# Sheet1.net
KiCad netlist of a schematic drawn in Altium Designer
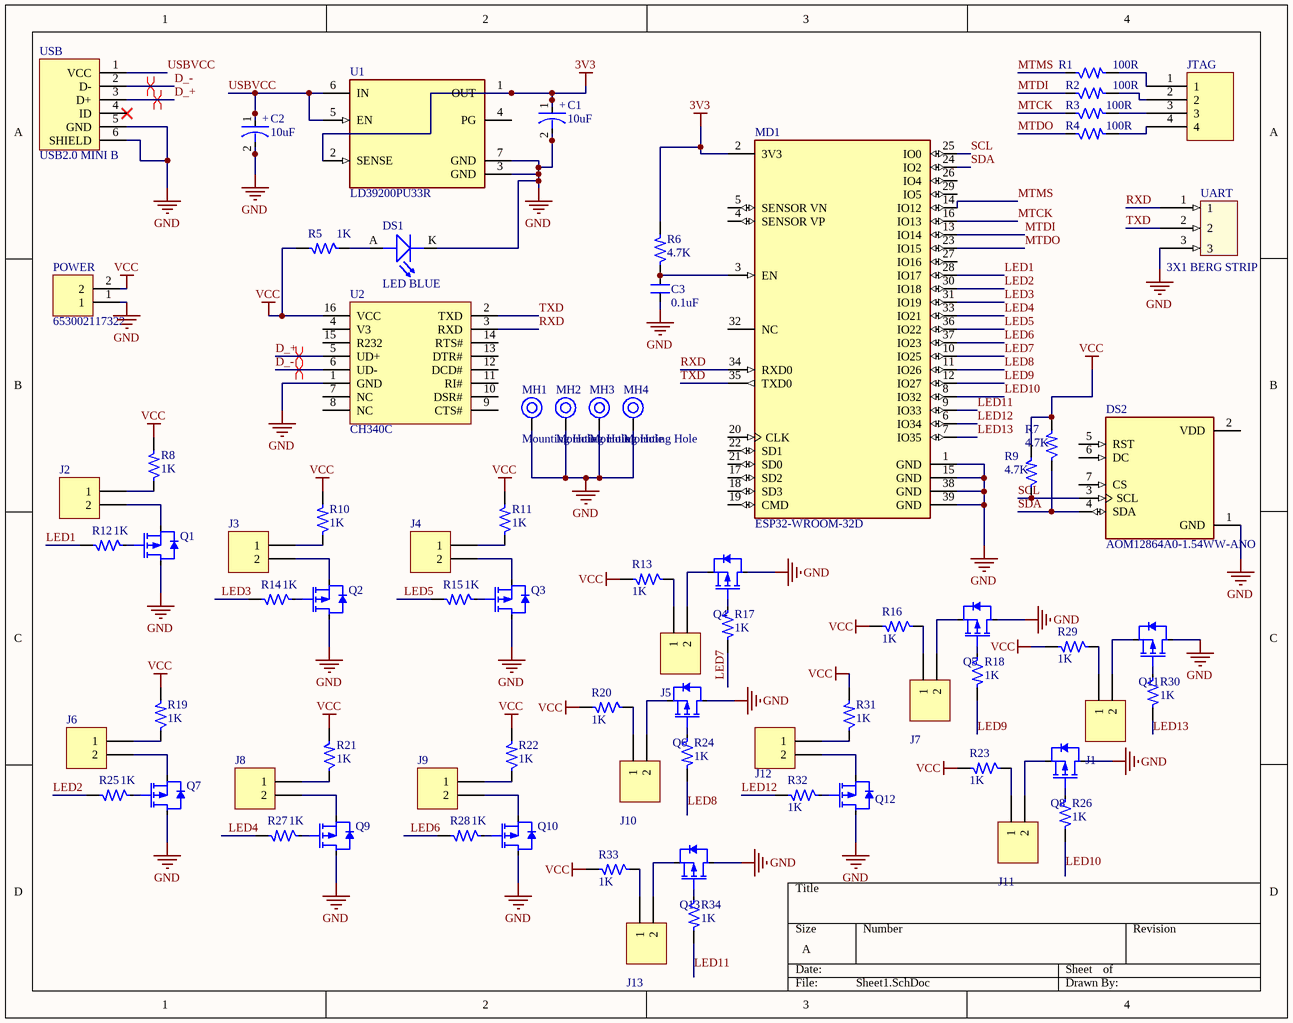
[diagram p0: Sheet1.SchDoc]

(export (version "E")
  (design (tool "Eeschema 10.0.6"))
  (components
    (comp (ref "C1")
      (value "10uF")
      (footprint "ACAP_P339_D393_H531_RAD")
      (description "10µF 400V Aluminum Electrolytic Capacitors Radial, Can - SMD 10000 Hrs @ 105°C")
      (fields
        (field (name "MANUFACTURER") "Nichicon")
        (field (name "MANUFACTURER PART NUMBER") "ULV2G100MNL1GS")
      )
      (libsource (lib "ESTEEMPCBLIB") (part "CAP-P_10uF-400V-20%-RAD"))
    )
    (comp (ref "C2")
      (value "10uF")
      (footprint "ACAP_P339_D393_H531_RAD")
      (description "10µF 400V Aluminum Electrolytic Capacitors Radial, Can - SMD 10000 Hrs @ 105°C")
      (fields
        (field (name "MANUFACTURER") "Nichicon")
        (field (name "MANUFACTURER PART NUMBER") "ULV2G100MNL1GS")
      )
      (libsource (lib "ESTEEMPCBLIB") (part "CAP-P_10uF-400V-20%-RAD"))
    )
    (comp (ref "C3")
      (value "0.1uF")
      (footprint "CAP_0805")
      (description "0.1µF ±5% 50V Ceramic Capacitor X7R 0805 (2012 Metric)")
      (fields
        (field (name "MANUFACTURER") "AVX Corporation")
        (field (name "MANUFACTURER PART NUMBER") "08055C104JAT4A")
      )
      (libsource (lib "ESTEEMPCBLIB") (part "CAP_0.1uF-50V-5%-0805"))
    )
    (comp (ref "DS1")
      (value "LED BLUE")
      (footprint "LED_0805")
      (description "Blue 470nm LED Indication - Discrete 3.3V 0805 (2012 Metric)")
      (fields
        (field (name "MANUFACTURER") "Vishay Lite-On")
        (field (name "MANUFACTURER PART NUMBER") "LTST-C171TBKT")
      )
      (libsource (lib "ESTEEMPCBLIB") (part "LED_BLUE-3V3-20mA-0805"))
    )
    (comp (ref "DS2")
      (value "AOM12864A0-1.54WW-ANO")
      (footprint "LCD_AOM12864A0-1.54WW-ANO")
      (description "Non-Touch Graphic LCD Display Module - White OLED SPI 1.54 (39.12mm) 128 x 64")
      (fields (field (name "MF") "Orient Display"))
      (libsource (lib "AOM12864A0-1.54WW-ANO") (part "AOM12864A0-1.54WW-ANO"))
    )
    (comp (ref "J1")
      (value "2X1 TERMINAL BLOCK")
      (footprint "CON2_P137_691103110002_TH_ST")
      (description "2 Pins, 1 Row 137mil Pitch, straight Connector, male")
      (fields
        (field (name "MANUFACTURER") "Wurth Electronics")
        (field (name "MANUFACTURER PART NUMBER") "691103110002")
      )
      (libsource (lib "") (part "CON-TB_2X1-137-ST-TH_1"))
    )
    (comp (ref "J2")
      (value "2X1 TERMINAL BLOCK")
      (footprint "CON2_P137_691103110002_TH_ST")
      (description "2 Pins, 1 Row 137mil Pitch, straight Connector, male")
      (fields
        (field (name "MANUFACTURER") "Wurth Electronics")
        (field (name "MANUFACTURER PART NUMBER") "691103110002")
      )
      (libsource (lib "ESTEEMPCBLIB") (part "CON-TB_2X1-137-ST-TH"))
    )
    (comp (ref "J3")
      (value "2X1 TERMINAL BLOCK")
      (footprint "CON2_P137_691103110002_TH_ST")
      (description "2 Pins, 1 Row 137mil Pitch, straight Connector, male")
      (fields
        (field (name "MANUFACTURER") "Wurth Electronics")
        (field (name "MANUFACTURER PART NUMBER") "691103110002")
      )
      (libsource (lib "ESTEEMPCBLIB") (part "CON-TB_2X1-137-ST-TH"))
    )
    (comp (ref "J4")
      (value "2X1 TERMINAL BLOCK")
      (footprint "CON2_P137_691103110002_TH_ST")
      (description "2 Pins, 1 Row 137mil Pitch, straight Connector, male")
      (fields
        (field (name "MANUFACTURER") "Wurth Electronics")
        (field (name "MANUFACTURER PART NUMBER") "691103110002")
      )
      (libsource (lib "ESTEEMPCBLIB") (part "CON-TB_2X1-137-ST-TH"))
    )
    (comp (ref "J5")
      (value "2X1 TERMINAL BLOCK")
      (footprint "CON2_P137_691103110002_TH_ST")
      (description "2 Pins, 1 Row 137mil Pitch, straight Connector, male")
      (fields
        (field (name "MANUFACTURER") "Wurth Electronics")
        (field (name "MANUFACTURER PART NUMBER") "691103110002")
      )
      (libsource (lib "") (part "CON-TB_2X1-137-ST-TH_1"))
    )
    (comp (ref "J6")
      (value "2X1 TERMINAL BLOCK")
      (footprint "CON2_P137_691103110002_TH_ST")
      (description "2 Pins, 1 Row 137mil Pitch, straight Connector, male")
      (fields
        (field (name "MANUFACTURER") "Wurth Electronics")
        (field (name "MANUFACTURER PART NUMBER") "691103110002")
      )
      (libsource (lib "ESTEEMPCBLIB") (part "CON-TB_2X1-137-ST-TH"))
    )
    (comp (ref "J7")
      (value "2X1 TERMINAL BLOCK")
      (footprint "CON2_P137_691103110002_TH_ST")
      (description "2 Pins, 1 Row 137mil Pitch, straight Connector, male")
      (fields
        (field (name "MANUFACTURER") "Wurth Electronics")
        (field (name "MANUFACTURER PART NUMBER") "691103110002")
      )
      (libsource (lib "") (part "CON-TB_2X1-137-ST-TH_1"))
    )
    (comp (ref "J8")
      (value "2X1 TERMINAL BLOCK")
      (footprint "CON2_P137_691103110002_TH_ST")
      (description "2 Pins, 1 Row 137mil Pitch, straight Connector, male")
      (fields
        (field (name "MANUFACTURER") "Wurth Electronics")
        (field (name "MANUFACTURER PART NUMBER") "691103110002")
      )
      (libsource (lib "ESTEEMPCBLIB") (part "CON-TB_2X1-137-ST-TH"))
    )
    (comp (ref "J9")
      (value "2X1 TERMINAL BLOCK")
      (footprint "CON2_P137_691103110002_TH_ST")
      (description "2 Pins, 1 Row 137mil Pitch, straight Connector, male")
      (fields
        (field (name "MANUFACTURER") "Wurth Electronics")
        (field (name "MANUFACTURER PART NUMBER") "691103110002")
      )
      (libsource (lib "ESTEEMPCBLIB") (part "CON-TB_2X1-137-ST-TH"))
    )
    (comp (ref "J10")
      (value "2X1 TERMINAL BLOCK")
      (footprint "CON2_P137_691103110002_TH_ST")
      (description "2 Pins, 1 Row 137mil Pitch, straight Connector, male")
      (fields
        (field (name "MANUFACTURER") "Wurth Electronics")
        (field (name "MANUFACTURER PART NUMBER") "691103110002")
      )
      (libsource (lib "") (part "CON-TB_2X1-137-ST-TH_1"))
    )
    (comp (ref "J11")
      (value "2X1 TERMINAL BLOCK")
      (footprint "CON2_P137_691103110002_TH_ST")
      (description "2 Pins, 1 Row 137mil Pitch, straight Connector, male")
      (fields
        (field (name "MANUFACTURER") "Wurth Electronics")
        (field (name "MANUFACTURER PART NUMBER") "691103110002")
      )
      (libsource (lib "") (part "CON-TB_2X1-137-ST-TH_1"))
    )
    (comp (ref "J12")
      (value "2X1 TERMINAL BLOCK")
      (footprint "CON2_P137_691103110002_TH_ST")
      (description "2 Pins, 1 Row 137mil Pitch, straight Connector, male")
      (fields
        (field (name "MANUFACTURER") "Wurth Electronics")
        (field (name "MANUFACTURER PART NUMBER") "691103110002")
      )
      (libsource (lib "ESTEEMPCBLIB") (part "CON-TB_2X1-137-ST-TH"))
    )
    (comp (ref "J13")
      (value "2X1 TERMINAL BLOCK")
      (footprint "CON2_P137_691103110002_TH_ST")
      (description "2 Pins, 1 Row 137mil Pitch, straight Connector, male")
      (fields
        (field (name "MANUFACTURER") "Wurth Electronics")
        (field (name "MANUFACTURER PART NUMBER") "691103110002")
      )
      (libsource (lib "") (part "CON-TB_2X1-137-ST-TH_1"))
    )
    (comp (ref "JTAG")
      (value "4X1 BERG STRIP")
      (footprint "CON4_100_40D72_TH_ST_MALE")
      (description "4 Pins, 1 Row 2.54mm Pitch, Straight bergstrip, Male")
      (fields (field (name "MANUFACTURER") "NA"))
      (libsource (lib "ESTEEMPCBLIB") (part "CON-BS-PLG_4X1-100-ST-TH"))
    )
    (comp (ref "MD1")
      (value "ESP32-WROOM-32D")
      (footprint "FP-ESP32-WROOM-32D-MFG")
      (description "WIFI MODULE 32MBITS SPI FLASH")
      (fields
        (field (name "OCTOPART") "https://octopart.com/esp32-wroom-32d-espressif+systems-91040050")
        (field (name "MANUFACTURER") "Espressif Systems")
      )
      (libsource (lib "Altium Content Vault") (part "a031a76f8c27026a7a7f4657ff233a3"))
    )
    (comp (ref "MH1")
      (value "Mounting Hole")
      (footprint "MOUNTING")
      (fields (field (name "MANUFACTURER PART NUMBER") "NA"))
      (libsource (lib "ESTEEMPCBLIB") (part "MH_3.5H_6D"))
    )
    (comp (ref "MH2")
      (value "Mounting Hole")
      (footprint "MOUNTING")
      (fields (field (name "MANUFACTURER PART NUMBER") "NA"))
      (libsource (lib "ESTEEMPCBLIB") (part "MH_3.5H_6D"))
    )
    (comp (ref "MH3")
      (value "Mounting Hole")
      (footprint "MOUNTING")
      (fields (field (name "MANUFACTURER PART NUMBER") "NA"))
      (libsource (lib "ESTEEMPCBLIB") (part "MH_3.5H_6D"))
    )
    (comp (ref "MH4")
      (value "Mounting Hole")
      (footprint "MOUNTING")
      (fields (field (name "MANUFACTURER PART NUMBER") "NA"))
      (libsource (lib "ESTEEMPCBLIB") (part "MH_3.5H_6D"))
    )
    (comp (ref "POWER")
      (value "653002117322")
      (footprint "CON2_50_653002117322_TH_RA")
      (description "1 Pins, 1 Row 256mil Pitch, Straight, Male")
      (fields (field (name "MANUFACTURER") "JST") (field (name "MATING PART NUMBER") "653002113322"))
      (libsource (lib "ESTEEMPCBLIB") (part "CON-PLG_2X1-50-RA-TH"))
    )
    (comp (ref "Q1")
      (value "SUD19P06-60-GE3")
      (footprint "TO-252_181_255_118X62_SMD")
      (description "P-Channel 60V 18.3A (Tc) 2.3W (Ta), 38.5W (Tc) Surface Mount TO-252, (D-Pak)")
      (fields (field (name "MANUFACTURER") "Vishay Siliconix"))
      (libsource (lib "ESTEEMPCBLIB") (part "MOSFET-P_60V-18A-TO252"))
    )
    (comp (ref "Q2")
      (value "SUD19P06-60-GE3")
      (footprint "TO-252_181_255_118X62_SMD")
      (description "P-Channel 60V 18.3A (Tc) 2.3W (Ta), 38.5W (Tc) Surface Mount TO-252, (D-Pak)")
      (fields (field (name "MANUFACTURER") "Vishay Siliconix"))
      (libsource (lib "ESTEEMPCBLIB") (part "MOSFET-P_60V-18A-TO252"))
    )
    (comp (ref "Q3")
      (value "SUD19P06-60-GE3")
      (footprint "TO-252_181_255_118X62_SMD")
      (description "P-Channel 60V 18.3A (Tc) 2.3W (Ta), 38.5W (Tc) Surface Mount TO-252, (D-Pak)")
      (fields (field (name "MANUFACTURER") "Vishay Siliconix"))
      (libsource (lib "ESTEEMPCBLIB") (part "MOSFET-P_60V-18A-TO252"))
    )
    (comp (ref "Q4")
      (value "SUD19P06-60-GE3")
      (footprint "TO-252_181_255_118X62_SMD")
      (description "P-Channel 60V 18.3A (Tc) 2.3W (Ta), 38.5W (Tc) Surface Mount TO-252, (D-Pak)")
      (fields (field (name "MANUFACTURER") "Vishay Siliconix"))
      (libsource (lib "ESTEEMPCBLIB") (part "MOSFET-P_60V-18A-TO252"))
    )
    (comp (ref "Q5")
      (value "SUD19P06-60-GE3")
      (footprint "TO-252_181_255_118X62_SMD")
      (description "P-Channel 60V 18.3A (Tc) 2.3W (Ta), 38.5W (Tc) Surface Mount TO-252, (D-Pak)")
      (fields (field (name "MANUFACTURER") "Vishay Siliconix"))
      (libsource (lib "ESTEEMPCBLIB") (part "MOSFET-P_60V-18A-TO252"))
    )
    (comp (ref "Q6")
      (value "SUD19P06-60-GE3")
      (footprint "TO-252_181_255_118X62_SMD")
      (description "P-Channel 60V 18.3A (Tc) 2.3W (Ta), 38.5W (Tc) Surface Mount TO-252, (D-Pak)")
      (fields (field (name "MANUFACTURER") "Vishay Siliconix"))
      (libsource (lib "ESTEEMPCBLIB") (part "MOSFET-P_60V-18A-TO252"))
    )
    (comp (ref "Q7")
      (value "SUD19P06-60-GE3")
      (footprint "TO-252_181_255_118X62_SMD")
      (description "P-Channel 60V 18.3A (Tc) 2.3W (Ta), 38.5W (Tc) Surface Mount TO-252, (D-Pak)")
      (fields (field (name "MANUFACTURER") "Vishay Siliconix"))
      (libsource (lib "ESTEEMPCBLIB") (part "MOSFET-P_60V-18A-TO252"))
    )
    (comp (ref "Q8")
      (value "SUD19P06-60-GE3")
      (footprint "TO-252_181_255_118X62_SMD")
      (description "P-Channel 60V 18.3A (Tc) 2.3W (Ta), 38.5W (Tc) Surface Mount TO-252, (D-Pak)")
      (fields (field (name "MANUFACTURER") "Vishay Siliconix"))
      (libsource (lib "ESTEEMPCBLIB") (part "MOSFET-P_60V-18A-TO252"))
    )
    (comp (ref "Q9")
      (value "SUD19P06-60-GE3")
      (footprint "TO-252_181_255_118X62_SMD")
      (description "P-Channel 60V 18.3A (Tc) 2.3W (Ta), 38.5W (Tc) Surface Mount TO-252, (D-Pak)")
      (fields (field (name "MANUFACTURER") "Vishay Siliconix"))
      (libsource (lib "ESTEEMPCBLIB") (part "MOSFET-P_60V-18A-TO252"))
    )
    (comp (ref "Q10")
      (value "SUD19P06-60-GE3")
      (footprint "TO-252_181_255_118X62_SMD")
      (description "P-Channel 60V 18.3A (Tc) 2.3W (Ta), 38.5W (Tc) Surface Mount TO-252, (D-Pak)")
      (fields (field (name "MANUFACTURER") "Vishay Siliconix"))
      (libsource (lib "ESTEEMPCBLIB") (part "MOSFET-P_60V-18A-TO252"))
    )
    (comp (ref "Q11")
      (value "SUD19P06-60-GE3")
      (footprint "TO-252_181_255_118X62_SMD")
      (description "P-Channel 60V 18.3A (Tc) 2.3W (Ta), 38.5W (Tc) Surface Mount TO-252, (D-Pak)")
      (fields (field (name "MANUFACTURER") "Vishay Siliconix"))
      (libsource (lib "ESTEEMPCBLIB") (part "MOSFET-P_60V-18A-TO252"))
    )
    (comp (ref "Q12")
      (value "SUD19P06-60-GE3")
      (footprint "TO-252_181_255_118X62_SMD")
      (description "P-Channel 60V 18.3A (Tc) 2.3W (Ta), 38.5W (Tc) Surface Mount TO-252, (D-Pak)")
      (fields (field (name "MANUFACTURER") "Vishay Siliconix"))
      (libsource (lib "ESTEEMPCBLIB") (part "MOSFET-P_60V-18A-TO252"))
    )
    (comp (ref "Q13")
      (value "SUD19P06-60-GE3")
      (footprint "TO-252_181_255_118X62_SMD")
      (description "P-Channel 60V 18.3A (Tc) 2.3W (Ta), 38.5W (Tc) Surface Mount TO-252, (D-Pak)")
      (fields (field (name "MANUFACTURER") "Vishay Siliconix"))
      (libsource (lib "ESTEEMPCBLIB") (part "MOSFET-P_60V-18A-TO252"))
    )
    (comp (ref "R1")
      (value "100R")
      (footprint "RES_0603")
      (description "100 Ohms ±1% 0.1W, 1/10W Chip Resistor 0603 (1608 Metric) Thick Film")
      (fields (field (name "MANUFACTURER") "Walsin") (field (name "MANUFACTURER PART NUMBER") "WR06X1000FTL"))
      (libsource (lib "ESTEEMPCBLIB") (part "RES_100R-0.1W-1%-0603"))
    )
    (comp (ref "R2")
      (value "100R")
      (footprint "RES_0603")
      (description "100 Ohms ±1% 0.1W, 1/10W Chip Resistor 0603 (1608 Metric) Thick Film")
      (fields (field (name "MANUFACTURER") "Walsin") (field (name "MANUFACTURER PART NUMBER") "WR06X1000FTL"))
      (libsource (lib "ESTEEMPCBLIB") (part "RES_100R-0.1W-1%-0603"))
    )
    (comp (ref "R3")
      (value "100R")
      (footprint "RES_0603")
      (description "100 Ohms ±1% 0.1W, 1/10W Chip Resistor 0603 (1608 Metric) Thick Film")
      (fields (field (name "MANUFACTURER") "Walsin") (field (name "MANUFACTURER PART NUMBER") "WR06X1000FTL"))
      (libsource (lib "ESTEEMPCBLIB") (part "RES_100R-0.1W-1%-0603"))
    )
    (comp (ref "R4")
      (value "100R")
      (footprint "RES_0603")
      (description "100 Ohms ±1% 0.1W, 1/10W Chip Resistor 0603 (1608 Metric) Thick Film")
      (fields (field (name "MANUFACTURER") "Walsin") (field (name "MANUFACTURER PART NUMBER") "WR06X1000FTL"))
      (libsource (lib "ESTEEMPCBLIB") (part "RES_100R-0.1W-1%-0603"))
    )
    (comp (ref "R5")
      (value "1K")
      (footprint "RES_0603")
      (description "1 kOhms ±1% 0.1W, 1/10W Chip Resistor 0603 (1608 Metric) Automotive AEC-Q200 Thick Film")
      (fields (field (name "MANUFACTURER") "Walsin") (field (name "MANUFACTURER PART NUMBER") "WR06X1001FTL"))
      (libsource (lib "ESTEEMPCBLIB") (part "RES_1K-0.1W-1%-0603"))
    )
    (comp (ref "R6")
      (value "4.7K")
      (footprint "RES_0603")
      (description "4.7 kOhms ±1% 0.1W, 1/10W Chip Resistor 0603 (1608 Metric) Moisture Resistant Thick Film")
      (fields (field (name "MANUFACTURER") "Walsin") (field (name "MANUFACTURER PART NUMBER") "WR06X4701FTL"))
      (libsource (lib "ESTEEMPCBLIB") (part "RES_4.7K-0.1W-1%-0603"))
    )
    (comp (ref "R7")
      (value "4.7K")
      (footprint "RES_0603")
      (description "4.7 kOhms ±1% 0.1W, 1/10W Chip Resistor 0603 (1608 Metric) Moisture Resistant Thick Film")
      (fields (field (name "MANUFACTURER") "Walsin") (field (name "MANUFACTURER PART NUMBER") "WR06X4701FTL"))
      (libsource (lib "ESTEEMPCBLIB") (part "RES_4.7K-0.1W-1%-0603"))
    )
    (comp (ref "R8")
      (value "1K")
      (footprint "RES_0603")
      (description "1 kOhms ±1% 0.1W, 1/10W Chip Resistor 0603 (1608 Metric) Automotive AEC-Q200 Thick Film")
      (fields (field (name "MANUFACTURER") "Walsin") (field (name "MANUFACTURER PART NUMBER") "WR06X1001FTL"))
      (libsource (lib "ESTEEMPCBLIB") (part "RES_1K-0.1W-1%-0603"))
    )
    (comp (ref "R9")
      (value "4.7K")
      (footprint "RES_0603")
      (description "4.7 kOhms ±1% 0.1W, 1/10W Chip Resistor 0603 (1608 Metric) Moisture Resistant Thick Film")
      (fields (field (name "MANUFACTURER") "Walsin") (field (name "MANUFACTURER PART NUMBER") "WR06X4701FTL"))
      (libsource (lib "ESTEEMPCBLIB") (part "RES_4.7K-0.1W-1%-0603"))
    )
    (comp (ref "R10")
      (value "1K")
      (footprint "RES_0603")
      (description "1 kOhms ±1% 0.1W, 1/10W Chip Resistor 0603 (1608 Metric) Automotive AEC-Q200 Thick Film")
      (fields (field (name "MANUFACTURER") "Walsin") (field (name "MANUFACTURER PART NUMBER") "WR06X1001FTL"))
      (libsource (lib "ESTEEMPCBLIB") (part "RES_1K-0.1W-1%-0603"))
    )
    (comp (ref "R11")
      (value "1K")
      (footprint "RES_0603")
      (description "1 kOhms ±1% 0.1W, 1/10W Chip Resistor 0603 (1608 Metric) Automotive AEC-Q200 Thick Film")
      (fields (field (name "MANUFACTURER") "Walsin") (field (name "MANUFACTURER PART NUMBER") "WR06X1001FTL"))
      (libsource (lib "ESTEEMPCBLIB") (part "RES_1K-0.1W-1%-0603"))
    )
    (comp (ref "R12")
      (value "1K")
      (footprint "RES_0603")
      (description "1 kOhms ±1% 0.1W, 1/10W Chip Resistor 0603 (1608 Metric) Automotive AEC-Q200 Thick Film")
      (fields (field (name "MANUFACTURER") "Walsin") (field (name "MANUFACTURER PART NUMBER") "WR06X1001FTL"))
      (libsource (lib "ESTEEMPCBLIB") (part "RES_1K-0.1W-1%-0603"))
    )
    (comp (ref "R13")
      (value "1K")
      (footprint "RES_0603")
      (description "1 kOhms ±1% 0.1W, 1/10W Chip Resistor 0603 (1608 Metric) Automotive AEC-Q200 Thick Film")
      (fields (field (name "MANUFACTURER") "Walsin") (field (name "MANUFACTURER PART NUMBER") "WR06X1001FTL"))
      (libsource (lib "ESTEEMPCBLIB") (part "RES_1K-0.1W-1%-0603"))
    )
    (comp (ref "R14")
      (value "1K")
      (footprint "RES_0603")
      (description "1 kOhms ±1% 0.1W, 1/10W Chip Resistor 0603 (1608 Metric) Automotive AEC-Q200 Thick Film")
      (fields (field (name "MANUFACTURER") "Walsin") (field (name "MANUFACTURER PART NUMBER") "WR06X1001FTL"))
      (libsource (lib "ESTEEMPCBLIB") (part "RES_1K-0.1W-1%-0603"))
    )
    (comp (ref "R15")
      (value "1K")
      (footprint "RES_0603")
      (description "1 kOhms ±1% 0.1W, 1/10W Chip Resistor 0603 (1608 Metric) Automotive AEC-Q200 Thick Film")
      (fields (field (name "MANUFACTURER") "Walsin") (field (name "MANUFACTURER PART NUMBER") "WR06X1001FTL"))
      (libsource (lib "ESTEEMPCBLIB") (part "RES_1K-0.1W-1%-0603"))
    )
    (comp (ref "R16")
      (value "1K")
      (footprint "RES_0603")
      (description "1 kOhms ±1% 0.1W, 1/10W Chip Resistor 0603 (1608 Metric) Automotive AEC-Q200 Thick Film")
      (fields (field (name "MANUFACTURER") "Walsin") (field (name "MANUFACTURER PART NUMBER") "WR06X1001FTL"))
      (libsource (lib "ESTEEMPCBLIB") (part "RES_1K-0.1W-1%-0603"))
    )
    (comp (ref "R17")
      (value "1K")
      (footprint "RES_0603")
      (description "1 kOhms ±1% 0.1W, 1/10W Chip Resistor 0603 (1608 Metric) Automotive AEC-Q200 Thick Film")
      (fields (field (name "MANUFACTURER") "Walsin") (field (name "MANUFACTURER PART NUMBER") "WR06X1001FTL"))
      (libsource (lib "ESTEEMPCBLIB") (part "RES_1K-0.1W-1%-0603"))
    )
    (comp (ref "R18")
      (value "1K")
      (footprint "RES_0603")
      (description "1 kOhms ±1% 0.1W, 1/10W Chip Resistor 0603 (1608 Metric) Automotive AEC-Q200 Thick Film")
      (fields (field (name "MANUFACTURER") "Walsin") (field (name "MANUFACTURER PART NUMBER") "WR06X1001FTL"))
      (libsource (lib "ESTEEMPCBLIB") (part "RES_1K-0.1W-1%-0603"))
    )
    (comp (ref "R19")
      (value "1K")
      (footprint "RES_0603")
      (description "1 kOhms ±1% 0.1W, 1/10W Chip Resistor 0603 (1608 Metric) Automotive AEC-Q200 Thick Film")
      (fields (field (name "MANUFACTURER") "Walsin") (field (name "MANUFACTURER PART NUMBER") "WR06X1001FTL"))
      (libsource (lib "ESTEEMPCBLIB") (part "RES_1K-0.1W-1%-0603"))
    )
    (comp (ref "R20")
      (value "1K")
      (footprint "RES_0603")
      (description "1 kOhms ±1% 0.1W, 1/10W Chip Resistor 0603 (1608 Metric) Automotive AEC-Q200 Thick Film")
      (fields (field (name "MANUFACTURER") "Walsin") (field (name "MANUFACTURER PART NUMBER") "WR06X1001FTL"))
      (libsource (lib "ESTEEMPCBLIB") (part "RES_1K-0.1W-1%-0603"))
    )
    (comp (ref "R21")
      (value "1K")
      (footprint "RES_0603")
      (description "1 kOhms ±1% 0.1W, 1/10W Chip Resistor 0603 (1608 Metric) Automotive AEC-Q200 Thick Film")
      (fields (field (name "MANUFACTURER") "Walsin") (field (name "MANUFACTURER PART NUMBER") "WR06X1001FTL"))
      (libsource (lib "ESTEEMPCBLIB") (part "RES_1K-0.1W-1%-0603"))
    )
    (comp (ref "R22")
      (value "1K")
      (footprint "RES_0603")
      (description "1 kOhms ±1% 0.1W, 1/10W Chip Resistor 0603 (1608 Metric) Automotive AEC-Q200 Thick Film")
      (fields (field (name "MANUFACTURER") "Walsin") (field (name "MANUFACTURER PART NUMBER") "WR06X1001FTL"))
      (libsource (lib "ESTEEMPCBLIB") (part "RES_1K-0.1W-1%-0603"))
    )
    (comp (ref "R23")
      (value "1K")
      (footprint "RES_0603")
      (description "1 kOhms ±1% 0.1W, 1/10W Chip Resistor 0603 (1608 Metric) Automotive AEC-Q200 Thick Film")
      (fields (field (name "MANUFACTURER") "Walsin") (field (name "MANUFACTURER PART NUMBER") "WR06X1001FTL"))
      (libsource (lib "ESTEEMPCBLIB") (part "RES_1K-0.1W-1%-0603"))
    )
    (comp (ref "R24")
      (value "1K")
      (footprint "RES_0603")
      (description "1 kOhms ±1% 0.1W, 1/10W Chip Resistor 0603 (1608 Metric) Automotive AEC-Q200 Thick Film")
      (fields (field (name "MANUFACTURER") "Walsin") (field (name "MANUFACTURER PART NUMBER") "WR06X1001FTL"))
      (libsource (lib "ESTEEMPCBLIB") (part "RES_1K-0.1W-1%-0603"))
    )
    (comp (ref "R25")
      (value "1K")
      (footprint "RES_0603")
      (description "1 kOhms ±1% 0.1W, 1/10W Chip Resistor 0603 (1608 Metric) Automotive AEC-Q200 Thick Film")
      (fields (field (name "MANUFACTURER") "Walsin") (field (name "MANUFACTURER PART NUMBER") "WR06X1001FTL"))
      (libsource (lib "ESTEEMPCBLIB") (part "RES_1K-0.1W-1%-0603"))
    )
    (comp (ref "R26")
      (value "1K")
      (footprint "RES_0603")
      (description "1 kOhms ±1% 0.1W, 1/10W Chip Resistor 0603 (1608 Metric) Automotive AEC-Q200 Thick Film")
      (fields (field (name "MANUFACTURER") "Walsin") (field (name "MANUFACTURER PART NUMBER") "WR06X1001FTL"))
      (libsource (lib "ESTEEMPCBLIB") (part "RES_1K-0.1W-1%-0603"))
    )
    (comp (ref "R27")
      (value "1K")
      (footprint "RES_0603")
      (description "1 kOhms ±1% 0.1W, 1/10W Chip Resistor 0603 (1608 Metric) Automotive AEC-Q200 Thick Film")
      (fields (field (name "MANUFACTURER") "Walsin") (field (name "MANUFACTURER PART NUMBER") "WR06X1001FTL"))
      (libsource (lib "ESTEEMPCBLIB") (part "RES_1K-0.1W-1%-0603"))
    )
    (comp (ref "R28")
      (value "1K")
      (footprint "RES_0603")
      (description "1 kOhms ±1% 0.1W, 1/10W Chip Resistor 0603 (1608 Metric) Automotive AEC-Q200 Thick Film")
      (fields (field (name "MANUFACTURER") "Walsin") (field (name "MANUFACTURER PART NUMBER") "WR06X1001FTL"))
      (libsource (lib "ESTEEMPCBLIB") (part "RES_1K-0.1W-1%-0603"))
    )
    (comp (ref "R29")
      (value "1K")
      (footprint "RES_0603")
      (description "1 kOhms ±1% 0.1W, 1/10W Chip Resistor 0603 (1608 Metric) Automotive AEC-Q200 Thick Film")
      (fields (field (name "MANUFACTURER") "Walsin") (field (name "MANUFACTURER PART NUMBER") "WR06X1001FTL"))
      (libsource (lib "ESTEEMPCBLIB") (part "RES_1K-0.1W-1%-0603"))
    )
    (comp (ref "R30")
      (value "1K")
      (footprint "RES_0603")
      (description "1 kOhms ±1% 0.1W, 1/10W Chip Resistor 0603 (1608 Metric) Automotive AEC-Q200 Thick Film")
      (fields (field (name "MANUFACTURER") "Walsin") (field (name "MANUFACTURER PART NUMBER") "WR06X1001FTL"))
      (libsource (lib "ESTEEMPCBLIB") (part "RES_1K-0.1W-1%-0603"))
    )
    (comp (ref "R31")
      (value "1K")
      (footprint "RES_0603")
      (description "1 kOhms ±1% 0.1W, 1/10W Chip Resistor 0603 (1608 Metric) Automotive AEC-Q200 Thick Film")
      (fields (field (name "MANUFACTURER") "Walsin") (field (name "MANUFACTURER PART NUMBER") "WR06X1001FTL"))
      (libsource (lib "ESTEEMPCBLIB") (part "RES_1K-0.1W-1%-0603"))
    )
    (comp (ref "R32")
      (value "1K")
      (footprint "RES_0603")
      (description "1 kOhms ±1% 0.1W, 1/10W Chip Resistor 0603 (1608 Metric) Automotive AEC-Q200 Thick Film")
      (fields (field (name "MANUFACTURER") "Walsin") (field (name "MANUFACTURER PART NUMBER") "WR06X1001FTL"))
      (libsource (lib "ESTEEMPCBLIB") (part "RES_1K-0.1W-1%-0603"))
    )
    (comp (ref "R33")
      (value "1K")
      (footprint "RES_0603")
      (description "1 kOhms ±1% 0.1W, 1/10W Chip Resistor 0603 (1608 Metric) Automotive AEC-Q200 Thick Film")
      (fields (field (name "MANUFACTURER") "Walsin") (field (name "MANUFACTURER PART NUMBER") "WR06X1001FTL"))
      (libsource (lib "ESTEEMPCBLIB") (part "RES_1K-0.1W-1%-0603"))
    )
    (comp (ref "R34")
      (value "1K")
      (footprint "RES_0603")
      (description "1 kOhms ±1% 0.1W, 1/10W Chip Resistor 0603 (1608 Metric) Automotive AEC-Q200 Thick Film")
      (fields (field (name "MANUFACTURER") "Walsin") (field (name "MANUFACTURER PART NUMBER") "WR06X1001FTL"))
      (libsource (lib "ESTEEMPCBLIB") (part "RES_1K-0.1W-1%-0603"))
    )
    (comp (ref "U1")
      (value "LD39200PU33R")
      (footprint "FP-DFN6-7946637-MFG")
      (description "IC REG LINEAR 3.3V 2A 6DFN")
      (libsource (lib "Altium Content Vault") (part "f0cfe00d12cb984572f50007c934a2d"))
    )
    (comp (ref "U2")
      (value "CH340C")
      (footprint "SOIC16_50_284_25X90_SMT")
      (description "USB Bridge, USB to UART USB 2.0 UART Interface")
      (fields (field (name "MANUFACTURER") "Olimex"))
      (libsource (lib "ESTEEMPCBLIB") (part "IC_CH340C"))
    )
    (comp (ref "UART")
      (value "3X1 BERG STRIP")
      (footprint "CON3_100_40D72_TH_ST-MALE")
      (description "3 Pins, 1 Row 2.54mm Pitch, Straight bergstrip, Male")
      (fields (field (name "MANUFACTURER PART NUMBER") "RKI-1140") (field (name "MANUFACTURER") "NA"))
      (libsource (lib "ESTEEMPCBLIB") (part "CON-BS-PLG_3X1-100-ST-TH"))
    )
    (comp (ref "USB")
      (value "USB2.0 MINI B")
      (footprint "CON_690-005-299-043")
      (description "USB - mini B USB 2.0 Receptacle Connector 5 Position Surface Mount, Right Angle")
      (fields
        (field (name "MANUFACTURER") "EDAC")
        (field (name "MANUFACTURER PART NUMBER") "690-005-299-043")
      )
      (libsource (lib "ESTEEMPCBLIB") (part "CON_USB2.0-MINIB-SMD"))
    )
  )
  (nets
    (net (code "1") (name "/D_+") (class "Default")
      (node (ref "U2") (pin "5") (pinfunction "UD+_5") (pintype "passive"))
      (node (ref "USB") (pin "3") (pinfunction "D+_3") (pintype "passive"))
    )
    (net (code "2") (name "/D_-") (class "Default")
      (node (ref "U2") (pin "6") (pinfunction "UD-_6") (pintype "passive"))
      (node (ref "USB") (pin "2") (pinfunction "D-_2") (pintype "passive"))
    )
    (net (code "3") (name "/LED1") (class "Default")
      (node (ref "MD1") (pin "28") (pinfunction "IO17_28") (pintype "bidirectional"))
      (node (ref "R12") (pin "2") (pinfunction "2_2") (pintype "passive"))
    )
    (net (code "4") (name "/LED2") (class "Default")
      (node (ref "MD1") (pin "30") (pinfunction "IO18_30") (pintype "bidirectional"))
      (node (ref "R25") (pin "2") (pinfunction "2_2") (pintype "passive"))
    )
    (net (code "5") (name "/LED3") (class "Default")
      (node (ref "MD1") (pin "31") (pinfunction "IO19_31") (pintype "bidirectional"))
      (node (ref "R14") (pin "2") (pinfunction "2_2") (pintype "passive"))
    )
    (net (code "6") (name "/LED4") (class "Default")
      (node (ref "MD1") (pin "33") (pinfunction "IO21_33") (pintype "bidirectional"))
      (node (ref "R27") (pin "2") (pinfunction "2_2") (pintype "passive"))
    )
    (net (code "7") (name "/LED5") (class "Default")
      (node (ref "MD1") (pin "36") (pinfunction "IO22_36") (pintype "bidirectional"))
      (node (ref "R15") (pin "2") (pinfunction "2_2") (pintype "passive"))
    )
    (net (code "8") (name "/LED6") (class "Default")
      (node (ref "MD1") (pin "37") (pinfunction "IO23_37") (pintype "bidirectional"))
      (node (ref "R28") (pin "2") (pinfunction "2_2") (pintype "passive"))
    )
    (net (code "9") (name "/LED7") (class "Default")
      (node (ref "MD1") (pin "10") (pinfunction "IO25_10") (pintype "bidirectional"))
      (node (ref "R17") (pin "2") (pinfunction "2_2") (pintype "passive"))
    )
    (net (code "10") (name "/LED8") (class "Default")
      (node (ref "MD1") (pin "11") (pinfunction "IO26_11") (pintype "bidirectional"))
      (node (ref "R24") (pin "2") (pinfunction "2_2") (pintype "passive"))
    )
    (net (code "11") (name "/LED9") (class "Default")
      (node (ref "MD1") (pin "12") (pinfunction "IO27_12") (pintype "bidirectional"))
      (node (ref "R18") (pin "2") (pinfunction "2_2") (pintype "passive"))
    )
    (net (code "12") (name "/LED10") (class "Default")
      (node (ref "MD1") (pin "8") (pinfunction "IO32_8") (pintype "bidirectional"))
      (node (ref "R26") (pin "2") (pinfunction "2_2") (pintype "passive"))
    )
    (net (code "13") (name "/LED11") (class "Default")
      (node (ref "MD1") (pin "9") (pinfunction "IO33_9") (pintype "bidirectional"))
      (node (ref "R34") (pin "2") (pinfunction "2_2") (pintype "passive"))
    )
    (net (code "14") (name "/LED12") (class "Default")
      (node (ref "MD1") (pin "6") (pinfunction "IO34_6") (pintype "bidirectional"))
      (node (ref "R32") (pin "2") (pinfunction "2_2") (pintype "passive"))
    )
    (net (code "15") (name "/LED13") (class "Default")
      (node (ref "MD1") (pin "7") (pinfunction "IO35_7") (pintype "bidirectional"))
      (node (ref "R30") (pin "2") (pinfunction "2_2") (pintype "passive"))
    )
    (net (code "16") (name "/MTCK") (class "Default")
      (node (ref "MD1") (pin "16") (pinfunction "IO13_16") (pintype "bidirectional"))
      (node (ref "R3") (pin "1") (pinfunction "1_1") (pintype "passive"))
    )
    (net (code "17") (name "/MTDI") (class "Default")
      (node (ref "MD1") (pin "13") (pinfunction "IO14_13") (pintype "bidirectional"))
      (node (ref "R2") (pin "1") (pinfunction "1_1") (pintype "passive"))
    )
    (net (code "18") (name "/MTDO") (class "Default")
      (node (ref "MD1") (pin "23") (pinfunction "IO15_23") (pintype "bidirectional"))
      (node (ref "R4") (pin "1") (pinfunction "1_1") (pintype "passive"))
    )
    (net (code "19") (name "/MTMS") (class "Default")
      (node (ref "MD1") (pin "14") (pinfunction "IO12_14") (pintype "bidirectional"))
      (node (ref "R1") (pin "1") (pinfunction "1_1") (pintype "passive"))
    )
    (net (code "20") (name "/RXD") (class "Default")
      (node (ref "MD1") (pin "34") (pinfunction "RXD0_34") (pintype "input"))
      (node (ref "U2") (pin "3") (pinfunction "RXD_3") (pintype "passive"))
      (node (ref "UART") (pin "1") (pinfunction "1_1") (pintype "input"))
    )
    (net (code "21") (name "/SCL") (class "Default")
      (node (ref "DS2") (pin "3") (pinfunction "SCL_3") (pintype "input"))
      (node (ref "MD1") (pin "25") (pinfunction "IO0_25") (pintype "bidirectional"))
      (node (ref "R9") (pin "1") (pinfunction "1_1") (pintype "passive"))
    )
    (net (code "22") (name "/SDA") (class "Default")
      (node (ref "DS2") (pin "4") (pinfunction "SDA_4") (pintype "bidirectional"))
      (node (ref "MD1") (pin "24") (pinfunction "IO2_24") (pintype "bidirectional"))
      (node (ref "R7") (pin "1") (pinfunction "1_1") (pintype "passive"))
    )
    (net (code "23") (name "/TXD") (class "Default")
      (node (ref "MD1") (pin "35") (pinfunction "TXD0_35") (pintype "output"))
      (node (ref "U2") (pin "2") (pinfunction "TXD_2") (pintype "passive"))
      (node (ref "UART") (pin "2") (pinfunction "2_2") (pintype "input"))
    )
    (net (code "24") (name "/USBVCC") (class "Default")
      (node (ref "C2") (pin "1") (pinfunction "1_1") (pintype "passive"))
      (node (ref "U1") (pin "5") (pinfunction "EN_5") (pintype "input"))
      (node (ref "U1") (pin "6") (pinfunction "IN_6") (pintype "power_in"))
      (node (ref "USB") (pin "1") (pinfunction "VCC_1") (pintype "passive"))
    )
    (net (code "25") (name "3V3") (class "Default")
      (node (ref "C1") (pin "1") (pinfunction "1_1") (pintype "passive"))
      (node (ref "MD1") (pin "2") (pinfunction "3V3_2") (pintype "power_in"))
      (node (ref "R6") (pin "2") (pinfunction "2_2") (pintype "passive"))
      (node (ref "U1") (pin "1") (pinfunction "OUT_1") (pintype "power_in"))
      (node (ref "U1") (pin "2") (pinfunction "SENSE_2") (pintype "input"))
    )
    (net (code "26") (name "GND") (class "Default")
      (node (ref "C1") (pin "2") (pinfunction "2_2") (pintype "passive"))
      (node (ref "C2") (pin "2") (pinfunction "2_2") (pintype "passive"))
      (node (ref "C3") (pin "1") (pinfunction "1_1") (pintype "passive"))
      (node (ref "DS1") (pin "K") (pinfunction "CATHODE_K") (pintype "passive"))
      (node (ref "DS2") (pin "1") (pinfunction "GND_1") (pintype "power_in"))
      (node (ref "MD1") (pin "1") (pinfunction "GND_1") (pintype "power_in"))
      (node (ref "MD1") (pin "15") (pinfunction "GND_15") (pintype "power_in"))
      (node (ref "MD1") (pin "38") (pinfunction "GND_38") (pintype "power_in"))
      (node (ref "MD1") (pin "39") (pinfunction "GND_39") (pintype "power_in"))
      (node (ref "MH1") (pin "1") (pinfunction "1_1") (pintype "passive"))
      (node (ref "MH2") (pin "1") (pinfunction "1_1") (pintype "passive"))
      (node (ref "MH3") (pin "1") (pinfunction "1_1") (pintype "passive"))
      (node (ref "MH4") (pin "1") (pinfunction "1_1") (pintype "passive"))
      (node (ref "POWER") (pin "1") (pinfunction "1_1") (pintype "passive"))
      (node (ref "Q1") (pin "2") (pinfunction "S_2") (pintype "passive"))
      (node (ref "Q10") (pin "2") (pinfunction "S_2") (pintype "passive"))
      (node (ref "Q11") (pin "2") (pinfunction "S_2") (pintype "passive"))
      (node (ref "Q12") (pin "2") (pinfunction "S_2") (pintype "passive"))
      (node (ref "Q13") (pin "2") (pinfunction "S_2") (pintype "passive"))
      (node (ref "Q2") (pin "2") (pinfunction "S_2") (pintype "passive"))
      (node (ref "Q3") (pin "2") (pinfunction "S_2") (pintype "passive"))
      (node (ref "Q4") (pin "2") (pinfunction "S_2") (pintype "passive"))
      (node (ref "Q5") (pin "2") (pinfunction "S_2") (pintype "passive"))
      (node (ref "Q6") (pin "2") (pinfunction "S_2") (pintype "passive"))
      (node (ref "Q7") (pin "2") (pinfunction "S_2") (pintype "passive"))
      (node (ref "Q8") (pin "2") (pinfunction "S_2") (pintype "passive"))
      (node (ref "Q9") (pin "2") (pinfunction "S_2") (pintype "passive"))
      (node (ref "U1") (pin "3") (pinfunction "GND_3") (pintype "power_in"))
      (node (ref "U1") (pin "7") (pinfunction "GND_7") (pintype "power_in"))
      (node (ref "U2") (pin "1") (pinfunction "GND_1") (pintype "passive"))
      (node (ref "UART") (pin "3") (pinfunction "3_3") (pintype "input"))
      (node (ref "USB") (pin "5") (pinfunction "GND_5") (pintype "passive"))
      (node (ref "USB") (pin "6") (pinfunction "SHIELD_6") (pintype "passive"))
    )
    (net (code "27") (name "Net-(DS1-ANODE)") (class "Default")
      (node (ref "DS1") (pin "A") (pinfunction "ANODE_A") (pintype "passive"))
      (node (ref "R5") (pin "1") (pinfunction "1_1") (pintype "passive"))
    )
    (net (code "28") (name "Net-(J1-Pad1)") (class "Default")
      (node (ref "J1") (pin "1") (pinfunction "1_1") (pintype "passive"))
      (node (ref "R29") (pin "1") (pinfunction "1_1") (pintype "passive"))
    )
    (net (code "29") (name "Net-(J2-Pad1)") (class "Default")
      (node (ref "J2") (pin "1") (pinfunction "1_1") (pintype "passive"))
      (node (ref "R8") (pin "1") (pinfunction "1_1") (pintype "passive"))
    )
    (net (code "30") (name "Net-(J3-Pad1)") (class "Default")
      (node (ref "J3") (pin "1") (pinfunction "1_1") (pintype "passive"))
      (node (ref "R10") (pin "1") (pinfunction "1_1") (pintype "passive"))
    )
    (net (code "31") (name "Net-(J4-Pad1)") (class "Default")
      (node (ref "J4") (pin "1") (pinfunction "1_1") (pintype "passive"))
      (node (ref "R11") (pin "1") (pinfunction "1_1") (pintype "passive"))
    )
    (net (code "32") (name "Net-(J5-Pad1)") (class "Default")
      (node (ref "J5") (pin "1") (pinfunction "1_1") (pintype "passive"))
      (node (ref "R13") (pin "1") (pinfunction "1_1") (pintype "passive"))
    )
    (net (code "33") (name "Net-(J6-Pad1)") (class "Default")
      (node (ref "J6") (pin "1") (pinfunction "1_1") (pintype "passive"))
      (node (ref "R19") (pin "1") (pinfunction "1_1") (pintype "passive"))
    )
    (net (code "34") (name "Net-(J7-Pad1)") (class "Default")
      (node (ref "J7") (pin "1") (pinfunction "1_1") (pintype "passive"))
      (node (ref "R16") (pin "1") (pinfunction "1_1") (pintype "passive"))
    )
    (net (code "35") (name "Net-(J8-Pad1)") (class "Default")
      (node (ref "J8") (pin "1") (pinfunction "1_1") (pintype "passive"))
      (node (ref "R21") (pin "1") (pinfunction "1_1") (pintype "passive"))
    )
    (net (code "36") (name "Net-(J9-Pad1)") (class "Default")
      (node (ref "J9") (pin "1") (pinfunction "1_1") (pintype "passive"))
      (node (ref "R22") (pin "1") (pinfunction "1_1") (pintype "passive"))
    )
    (net (code "37") (name "Net-(J10-Pad1)") (class "Default")
      (node (ref "J10") (pin "1") (pinfunction "1_1") (pintype "passive"))
      (node (ref "R20") (pin "1") (pinfunction "1_1") (pintype "passive"))
    )
    (net (code "38") (name "Net-(J11-Pad1)") (class "Default")
      (node (ref "J11") (pin "1") (pinfunction "1_1") (pintype "passive"))
      (node (ref "R23") (pin "1") (pinfunction "1_1") (pintype "passive"))
    )
    (net (code "39") (name "Net-(J12-Pad1)") (class "Default")
      (node (ref "J12") (pin "1") (pinfunction "1_1") (pintype "passive"))
      (node (ref "R31") (pin "1") (pinfunction "1_1") (pintype "passive"))
    )
    (net (code "40") (name "Net-(J13-Pad1)") (class "Default")
      (node (ref "J13") (pin "1") (pinfunction "1_1") (pintype "passive"))
      (node (ref "R33") (pin "1") (pinfunction "1_1") (pintype "passive"))
    )
    (net (code "41") (name "Net-(JTAG-Pad1)") (class "Default")
      (node (ref "JTAG") (pin "1") (pinfunction "1_1") (pintype "passive"))
      (node (ref "R1") (pin "2") (pinfunction "2_2") (pintype "passive"))
    )
    (net (code "42") (name "Net-(JTAG-Pad2)") (class "Default")
      (node (ref "JTAG") (pin "2") (pinfunction "2_2") (pintype "passive"))
      (node (ref "R2") (pin "2") (pinfunction "2_2") (pintype "passive"))
    )
    (net (code "43") (name "Net-(JTAG-Pad3)") (class "Default")
      (node (ref "JTAG") (pin "3") (pinfunction "3_3") (pintype "passive"))
      (node (ref "R3") (pin "2") (pinfunction "2_2") (pintype "passive"))
    )
    (net (code "44") (name "Net-(JTAG-Pad4)") (class "Default")
      (node (ref "JTAG") (pin "4") (pinfunction "4_4") (pintype "passive"))
      (node (ref "R4") (pin "2") (pinfunction "2_2") (pintype "passive"))
    )
    (net (code "45") (name "Net-(MD1-EN)") (class "Default")
      (node (ref "C3") (pin "2") (pinfunction "2_2") (pintype "passive"))
      (node (ref "MD1") (pin "3") (pinfunction "EN_3") (pintype "input"))
      (node (ref "R6") (pin "1") (pinfunction "1_1") (pintype "passive"))
    )
    (net (code "46") (name "Net-(Q1-D)") (class "Default")
      (node (ref "J2") (pin "2") (pinfunction "2_2") (pintype "passive"))
      (node (ref "Q1") (pin "3") (pinfunction "D_3") (pintype "passive"))
    )
    (net (code "47") (name "Net-(Q1-G)") (class "Default")
      (node (ref "Q1") (pin "1") (pinfunction "G_1") (pintype "passive"))
      (node (ref "R12") (pin "1") (pinfunction "1_1") (pintype "passive"))
    )
    (net (code "48") (name "Net-(Q2-D)") (class "Default")
      (node (ref "J3") (pin "2") (pinfunction "2_2") (pintype "passive"))
      (node (ref "Q2") (pin "3") (pinfunction "D_3") (pintype "passive"))
    )
    (net (code "49") (name "Net-(Q2-G)") (class "Default")
      (node (ref "Q2") (pin "1") (pinfunction "G_1") (pintype "passive"))
      (node (ref "R14") (pin "1") (pinfunction "1_1") (pintype "passive"))
    )
    (net (code "50") (name "Net-(Q3-D)") (class "Default")
      (node (ref "J4") (pin "2") (pinfunction "2_2") (pintype "passive"))
      (node (ref "Q3") (pin "3") (pinfunction "D_3") (pintype "passive"))
    )
    (net (code "51") (name "Net-(Q3-G)") (class "Default")
      (node (ref "Q3") (pin "1") (pinfunction "G_1") (pintype "passive"))
      (node (ref "R15") (pin "1") (pinfunction "1_1") (pintype "passive"))
    )
    (net (code "52") (name "Net-(Q4-D)") (class "Default")
      (node (ref "J5") (pin "2") (pinfunction "2_2") (pintype "passive"))
      (node (ref "Q4") (pin "3") (pinfunction "D_3") (pintype "passive"))
    )
    (net (code "53") (name "Net-(Q4-G)") (class "Default")
      (node (ref "Q4") (pin "1") (pinfunction "G_1") (pintype "passive"))
      (node (ref "R17") (pin "1") (pinfunction "1_1") (pintype "passive"))
    )
    (net (code "54") (name "Net-(Q5-D)") (class "Default")
      (node (ref "J7") (pin "2") (pinfunction "2_2") (pintype "passive"))
      (node (ref "Q5") (pin "3") (pinfunction "D_3") (pintype "passive"))
    )
    (net (code "55") (name "Net-(Q5-G)") (class "Default")
      (node (ref "Q5") (pin "1") (pinfunction "G_1") (pintype "passive"))
      (node (ref "R18") (pin "1") (pinfunction "1_1") (pintype "passive"))
    )
    (net (code "56") (name "Net-(Q6-D)") (class "Default")
      (node (ref "J10") (pin "2") (pinfunction "2_2") (pintype "passive"))
      (node (ref "Q6") (pin "3") (pinfunction "D_3") (pintype "passive"))
    )
    (net (code "57") (name "Net-(Q6-G)") (class "Default")
      (node (ref "Q6") (pin "1") (pinfunction "G_1") (pintype "passive"))
      (node (ref "R24") (pin "1") (pinfunction "1_1") (pintype "passive"))
    )
    (net (code "58") (name "Net-(Q7-D)") (class "Default")
      (node (ref "J6") (pin "2") (pinfunction "2_2") (pintype "passive"))
      (node (ref "Q7") (pin "3") (pinfunction "D_3") (pintype "passive"))
    )
    (net (code "59") (name "Net-(Q7-G)") (class "Default")
      (node (ref "Q7") (pin "1") (pinfunction "G_1") (pintype "passive"))
      (node (ref "R25") (pin "1") (pinfunction "1_1") (pintype "passive"))
    )
    (net (code "60") (name "Net-(Q8-D)") (class "Default")
      (node (ref "J11") (pin "2") (pinfunction "2_2") (pintype "passive"))
      (node (ref "Q8") (pin "3") (pinfunction "D_3") (pintype "passive"))
    )
    (net (code "61") (name "Net-(Q8-G)") (class "Default")
      (node (ref "Q8") (pin "1") (pinfunction "G_1") (pintype "passive"))
      (node (ref "R26") (pin "1") (pinfunction "1_1") (pintype "passive"))
    )
    (net (code "62") (name "Net-(Q9-D)") (class "Default")
      (node (ref "J8") (pin "2") (pinfunction "2_2") (pintype "passive"))
      (node (ref "Q9") (pin "3") (pinfunction "D_3") (pintype "passive"))
    )
    (net (code "63") (name "Net-(Q9-G)") (class "Default")
      (node (ref "Q9") (pin "1") (pinfunction "G_1") (pintype "passive"))
      (node (ref "R27") (pin "1") (pinfunction "1_1") (pintype "passive"))
    )
    (net (code "64") (name "Net-(Q10-D)") (class "Default")
      (node (ref "J9") (pin "2") (pinfunction "2_2") (pintype "passive"))
      (node (ref "Q10") (pin "3") (pinfunction "D_3") (pintype "passive"))
    )
    (net (code "65") (name "Net-(Q10-G)") (class "Default")
      (node (ref "Q10") (pin "1") (pinfunction "G_1") (pintype "passive"))
      (node (ref "R28") (pin "1") (pinfunction "1_1") (pintype "passive"))
    )
    (net (code "66") (name "Net-(Q11-D)") (class "Default")
      (node (ref "J1") (pin "2") (pinfunction "2_2") (pintype "passive"))
      (node (ref "Q11") (pin "3") (pinfunction "D_3") (pintype "passive"))
    )
    (net (code "67") (name "Net-(Q11-G)") (class "Default")
      (node (ref "Q11") (pin "1") (pinfunction "G_1") (pintype "passive"))
      (node (ref "R30") (pin "1") (pinfunction "1_1") (pintype "passive"))
    )
    (net (code "68") (name "Net-(Q12-D)") (class "Default")
      (node (ref "J12") (pin "2") (pinfunction "2_2") (pintype "passive"))
      (node (ref "Q12") (pin "3") (pinfunction "D_3") (pintype "passive"))
    )
    (net (code "69") (name "Net-(Q12-G)") (class "Default")
      (node (ref "Q12") (pin "1") (pinfunction "G_1") (pintype "passive"))
      (node (ref "R32") (pin "1") (pinfunction "1_1") (pintype "passive"))
    )
    (net (code "70") (name "Net-(Q13-D)") (class "Default")
      (node (ref "J13") (pin "2") (pinfunction "2_2") (pintype "passive"))
      (node (ref "Q13") (pin "3") (pinfunction "D_3") (pintype "passive"))
    )
    (net (code "71") (name "Net-(Q13-G)") (class "Default")
      (node (ref "Q13") (pin "1") (pinfunction "G_1") (pintype "passive"))
      (node (ref "R34") (pin "1") (pinfunction "1_1") (pintype "passive"))
    )
    (net (code "72") (name "VCC") (class "Default")
      (node (ref "POWER") (pin "2") (pinfunction "2_2") (pintype "passive"))
      (node (ref "R10") (pin "2") (pinfunction "2_2") (pintype "passive"))
      (node (ref "R11") (pin "2") (pinfunction "2_2") (pintype "passive"))
      (node (ref "R13") (pin "2") (pinfunction "2_2") (pintype "passive"))
      (node (ref "R16") (pin "2") (pinfunction "2_2") (pintype "passive"))
      (node (ref "R19") (pin "2") (pinfunction "2_2") (pintype "passive"))
      (node (ref "R20") (pin "2") (pinfunction "2_2") (pintype "passive"))
      (node (ref "R21") (pin "2") (pinfunction "2_2") (pintype "passive"))
      (node (ref "R22") (pin "2") (pinfunction "2_2") (pintype "passive"))
      (node (ref "R23") (pin "2") (pinfunction "2_2") (pintype "passive"))
      (node (ref "R29") (pin "2") (pinfunction "2_2") (pintype "passive"))
      (node (ref "R31") (pin "2") (pinfunction "2_2") (pintype "passive"))
      (node (ref "R33") (pin "2") (pinfunction "2_2") (pintype "passive"))
      (node (ref "R5") (pin "2") (pinfunction "2_2") (pintype "passive"))
      (node (ref "R7") (pin "2") (pinfunction "2_2") (pintype "passive"))
      (node (ref "R8") (pin "2") (pinfunction "2_2") (pintype "passive"))
      (node (ref "R9") (pin "2") (pinfunction "2_2") (pintype "passive"))
      (node (ref "U2") (pin "16") (pinfunction "VCC_16") (pintype "passive"))
    )
    (net (code "73") (name "unconnected-(DS2-CS-Pad7)") (class "Default")
      (node (ref "DS2") (pin "7") (pinfunction "CS_7") (pintype "input"))
    )
    (net (code "74") (name "unconnected-(DS2-DC-Pad6)") (class "Default")
      (node (ref "DS2") (pin "6") (pinfunction "DC_6") (pintype "input"))
    )
    (net (code "75") (name "unconnected-(DS2-RST-Pad5)") (class "Default")
      (node (ref "DS2") (pin "5") (pinfunction "RST_5") (pintype "input"))
    )
    (net (code "76") (name "unconnected-(DS2-VDD-Pad2)") (class "Default")
      (node (ref "DS2") (pin "2") (pinfunction "VDD_2") (pintype "power_in"))
    )
    (net (code "77") (name "unconnected-(MD1-CLK-Pad20)") (class "Default")
      (node (ref "MD1") (pin "20") (pinfunction "CLK_20") (pintype "input"))
    )
    (net (code "78") (name "unconnected-(MD1-CMD-Pad19)") (class "Default")
      (node (ref "MD1") (pin "19") (pinfunction "CMD_19") (pintype "bidirectional"))
    )
    (net (code "79") (name "unconnected-(MD1-IO4-Pad26)") (class "Default")
      (node (ref "MD1") (pin "26") (pinfunction "IO4_26") (pintype "bidirectional"))
    )
    (net (code "80") (name "unconnected-(MD1-IO5-Pad29)") (class "Default")
      (node (ref "MD1") (pin "29") (pinfunction "IO5_29") (pintype "bidirectional"))
    )
    (net (code "81") (name "unconnected-(MD1-IO16-Pad27)") (class "Default")
      (node (ref "MD1") (pin "27") (pinfunction "IO16_27") (pintype "bidirectional"))
    )
    (net (code "82") (name "unconnected-(MD1-NC-Pad32)") (class "Default")
      (node (ref "MD1") (pin "32") (pinfunction "NC_32") (pintype "passive"))
    )
    (net (code "83") (name "unconnected-(MD1-SD0-Pad21)") (class "Default")
      (node (ref "MD1") (pin "21") (pinfunction "SD0_21") (pintype "bidirectional"))
    )
    (net (code "84") (name "unconnected-(MD1-SD1-Pad22)") (class "Default")
      (node (ref "MD1") (pin "22") (pinfunction "SD1_22") (pintype "bidirectional"))
    )
    (net (code "85") (name "unconnected-(MD1-SD2-Pad17)") (class "Default")
      (node (ref "MD1") (pin "17") (pinfunction "SD2_17") (pintype "bidirectional"))
    )
    (net (code "86") (name "unconnected-(MD1-SD3-Pad18)") (class "Default")
      (node (ref "MD1") (pin "18") (pinfunction "SD3_18") (pintype "bidirectional"))
    )
    (net (code "87") (name "unconnected-(MD1-SENSOR_VN-Pad5)") (class "Default")
      (node (ref "MD1") (pin "5") (pinfunction "SENSOR_VN_5") (pintype "bidirectional"))
    )
    (net (code "88") (name "unconnected-(MD1-SENSOR_VP-Pad4)") (class "Default")
      (node (ref "MD1") (pin "4") (pinfunction "SENSOR_VP_4") (pintype "bidirectional"))
    )
    (net (code "89") (name "unconnected-(U1-PG-Pad4)") (class "Default")
      (node (ref "U1") (pin "4") (pinfunction "PG_4") (pintype "open_collector"))
    )
    (net (code "90") (name "unconnected-(U2-CTS#-Pad9)") (class "Default")
      (node (ref "U2") (pin "9") (pinfunction "CTS#_9") (pintype "passive"))
    )
    (net (code "91") (name "unconnected-(U2-DCD#-Pad12)") (class "Default")
      (node (ref "U2") (pin "12") (pinfunction "DCD#_12") (pintype "passive"))
    )
    (net (code "92") (name "unconnected-(U2-DSR#-Pad10)") (class "Default")
      (node (ref "U2") (pin "10") (pinfunction "DSR#_10") (pintype "passive"))
    )
    (net (code "93") (name "unconnected-(U2-DTR#-Pad13)") (class "Default")
      (node (ref "U2") (pin "13") (pinfunction "DTR#_13") (pintype "passive"))
    )
    (net (code "94") (name "unconnected-(U2-NC-Pad7)") (class "Default")
      (node (ref "U2") (pin "7") (pinfunction "NC_7") (pintype "passive"))
    )
    (net (code "95") (name "unconnected-(U2-NC-Pad8)") (class "Default")
      (node (ref "U2") (pin "8") (pinfunction "NC_8") (pintype "passive"))
    )
    (net (code "96") (name "unconnected-(U2-R232-Pad15)") (class "Default")
      (node (ref "U2") (pin "15") (pinfunction "R232_15") (pintype "passive"))
    )
    (net (code "97") (name "unconnected-(U2-RI#-Pad11)") (class "Default")
      (node (ref "U2") (pin "11") (pinfunction "RI#_11") (pintype "passive"))
    )
    (net (code "98") (name "unconnected-(U2-RTS#-Pad14)") (class "Default")
      (node (ref "U2") (pin "14") (pinfunction "RTS#_14") (pintype "passive"))
    )
    (net (code "99") (name "unconnected-(U2-V3-Pad4)") (class "Default")
      (node (ref "U2") (pin "4") (pinfunction "V3_4") (pintype "passive"))
    )
    (net (code "100") (name "unconnected-(USB-ID-Pad4)") (class "Default")
      (node (ref "USB") (pin "4") (pinfunction "ID_4") (pintype "passive+no_connect"))
    )
  )
)
